# CPU_Module.net
KiCad netlist of a schematic drawn in Altium Designer
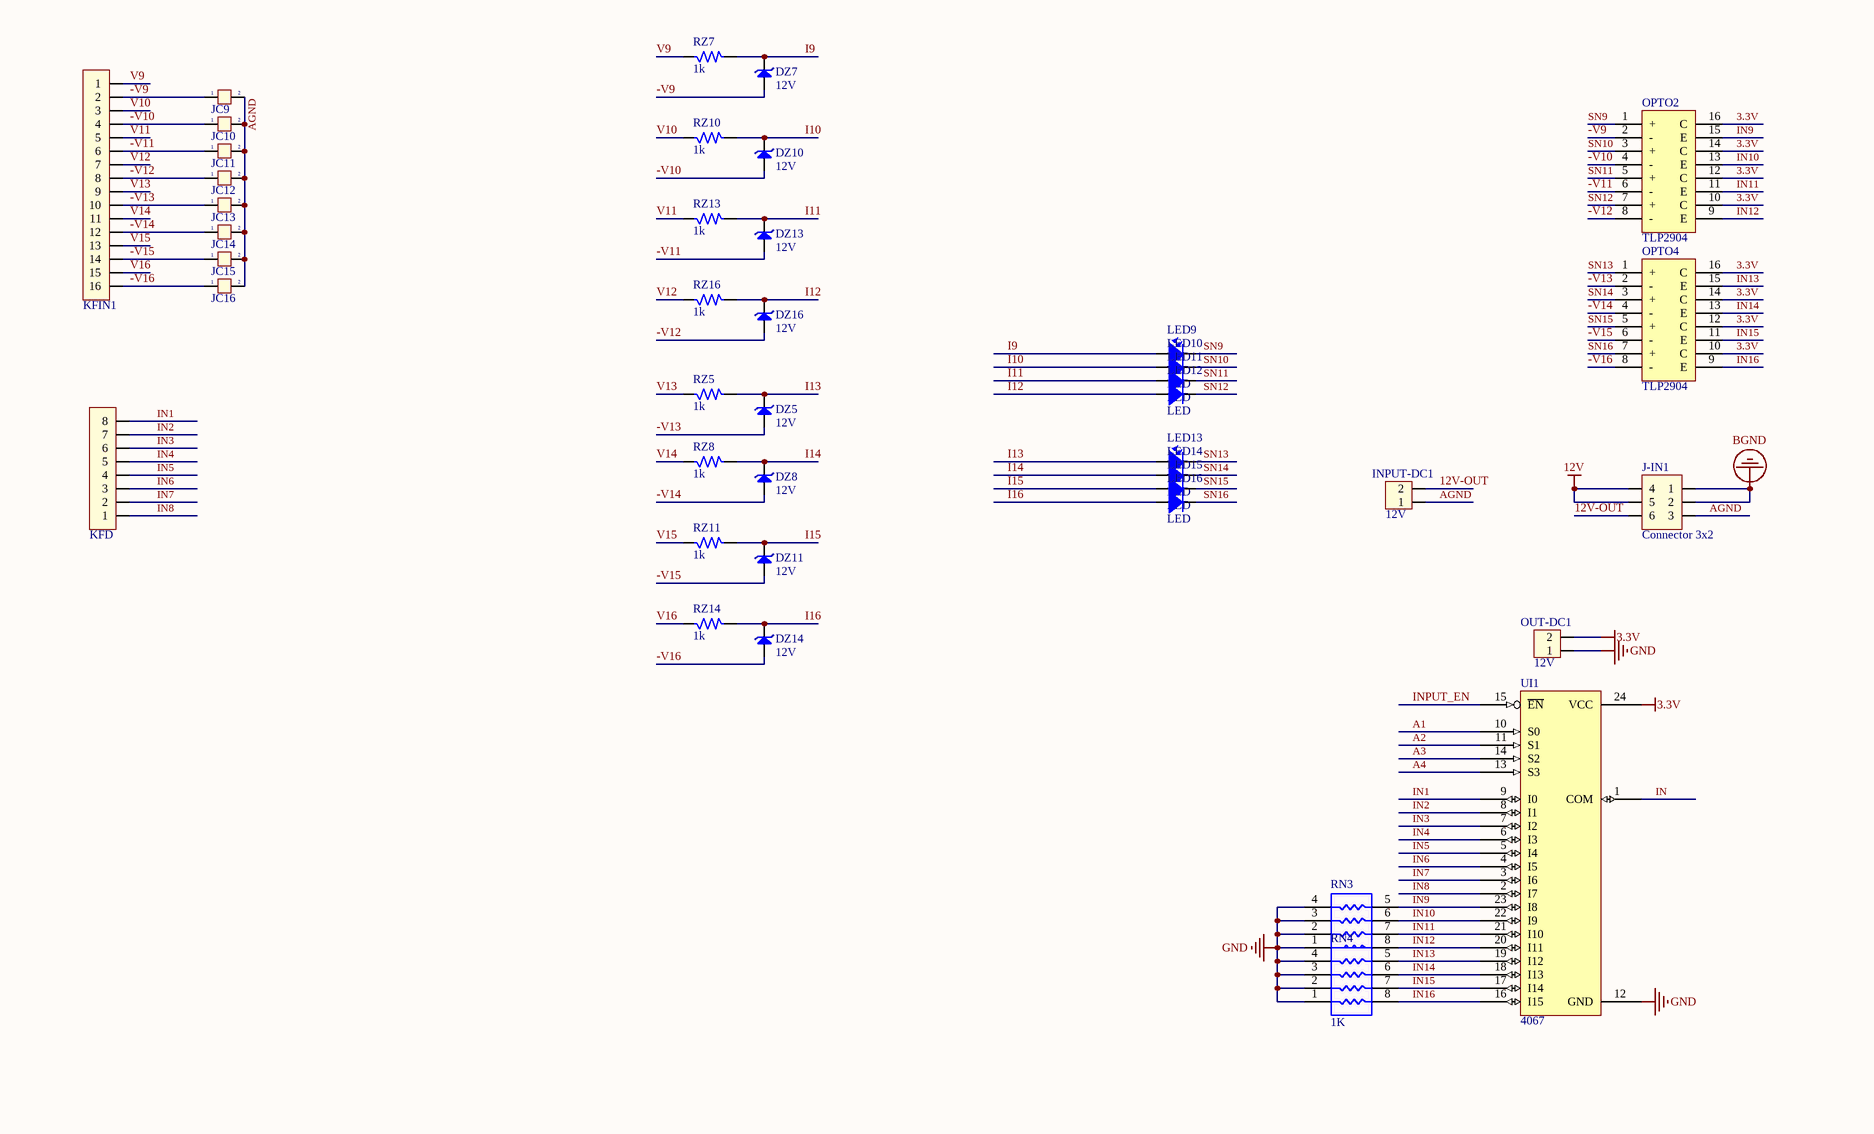
[diagram p0: CPU Module.SchDoc, top]
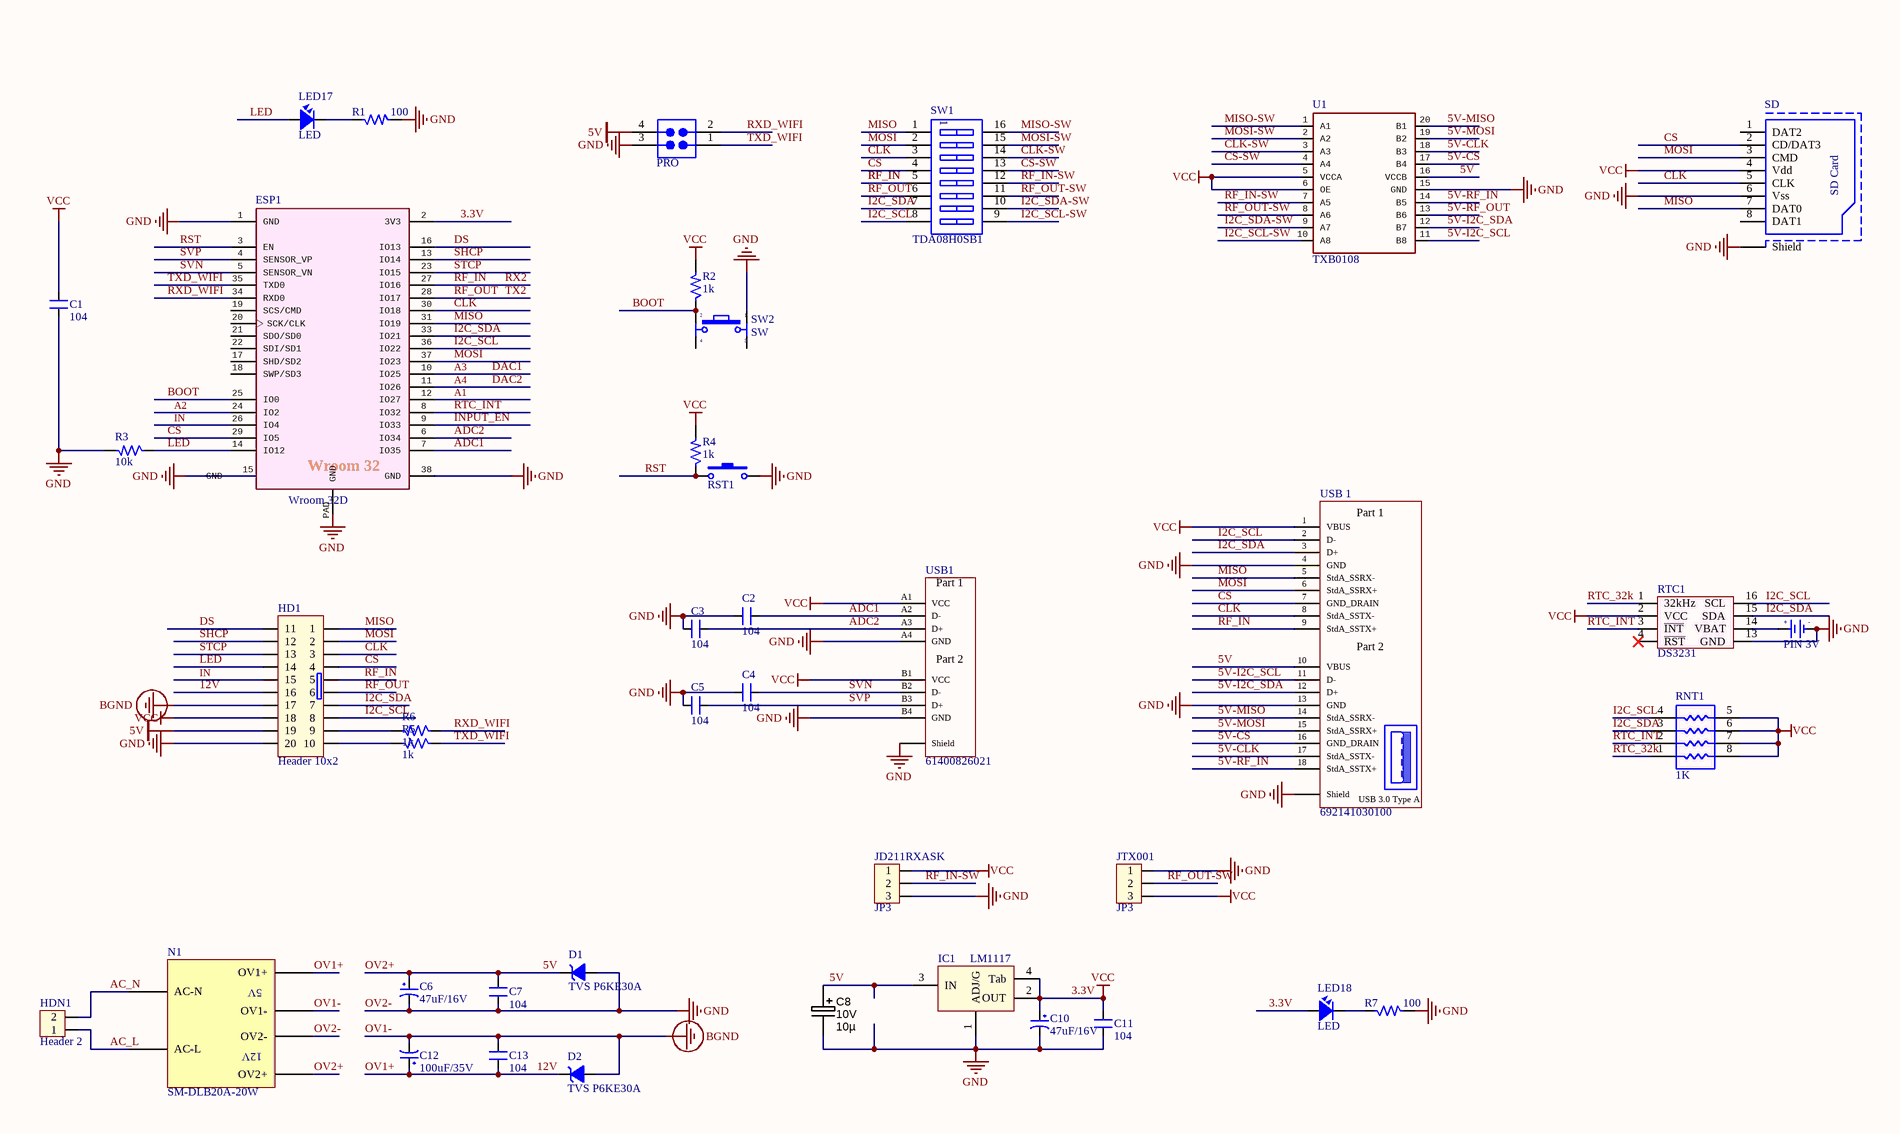
[diagram p1: CPU Module.SchDoc, bottom]

(export (version "E")
  (design (tool "Eeschema 10.0.6"))
  (components
    (comp (ref "BT1")
      (value "PIN 3V")
      (footprint "PIN CR1220-SMD")
      (description "Lithium Battery Holder for CR2032 3V Cell")
      (libsource (lib "Library") (part "PIN 3V"))
    )
    (comp (ref "C1")
      (value "104")
      (footprint "SM-0805")
      (description "Cap SMD")
      (libsource (lib "syhaunguyen") (part "CM"))
    )
    (comp (ref "C2")
      (value "104")
      (footprint "SM-0805")
      (description "Cap SMD")
      (libsource (lib "syhaunguyen") (part "CM"))
    )
    (comp (ref "C3")
      (value "104")
      (footprint "SM-0805")
      (description "Cap SMD")
      (libsource (lib "syhaunguyen") (part "CM"))
    )
    (comp (ref "C4")
      (value "104")
      (footprint "SM-0805")
      (description "Cap SMD")
      (libsource (lib "syhaunguyen") (part "CM"))
    )
    (comp (ref "C5")
      (value "104")
      (footprint "SM-0805")
      (description "Cap SMD")
      (libsource (lib "syhaunguyen") (part "CM"))
    )
    (comp (ref "C6")
      (value "47uF/16V")
      (footprint "WCAP-AS5H_6.3x5.5")
      (description "Cap 100uF/35V - 470uF/16V")
      (libsource (lib "syhaunguyen") (part "CP3"))
    )
    (comp (ref "C7")
      (value "104")
      (footprint "SM-0805")
      (description "Cap SMD")
      (libsource (lib "syhaunguyen") (part "CM"))
    )
    (comp (ref "C8")
      (value "10µ")
      (footprint "CAPMP3216X180N")
      (description "Capacitor SMD Tantalum 10uF 20% 10V 0805")
      (fields (field (name "TOLERANCE") "±20%") (field (name "RATINGS") "10V"))
      (libsource (lib "PBL - Capacitors") (part "CAPT_10u_0805_10V"))
    )
    (comp (ref "C10")
      (value "47uF/16V")
      (footprint "WCAP-AS5H_6.3x5.5")
      (description "Cap 100uF/35V - 470uF/16V")
      (libsource (lib "") (part "CP3_1"))
    )
    (comp (ref "C11")
      (value "104")
      (footprint "SM-0805")
      (description "Cap SMD")
      (libsource (lib "syhaunguyen") (part "CM"))
    )
    (comp (ref "C12")
      (value "100uF/35V")
      (footprint "WCAP-AS5H_8x10.5")
      (description "Cap 100uF/35V - 470uF/16V")
      (libsource (lib "syhaunguyen") (part "CP3"))
    )
    (comp (ref "C13")
      (value "104")
      (footprint "SM-0805")
      (description "Cap SMD")
      (libsource (lib "syhaunguyen") (part "CM"))
    )
    (comp (ref "D1")
      (value "TVS P6KE30A")
      (footprint "DO-214AA_Unidirectional")
      (description "Diode Zenner")
      (libsource (lib "syhaunguyen") (part "DZ"))
    )
    (comp (ref "D2")
      (value "TVS P6KE30A")
      (footprint "DO-214AA_Unidirectional")
      (description "Diode Zenner")
      (libsource (lib "syhaunguyen") (part "DZ"))
    )
    (comp (ref "DZ5")
      (value "12V")
      (footprint "DIOS 1S2P1406H")
      (description "DIODE GEN PURP 75V 200MA LLDS")
      (libsource (lib "Diode") (part "DIODE Zener"))
    )
    (comp (ref "DZ7")
      (value "12V")
      (footprint "DIOS 1S2P1406H")
      (description "DIODE GEN PURP 75V 200MA LLDS")
      (libsource (lib "Diode") (part "DIODE Zener"))
    )
    (comp (ref "DZ8")
      (value "12V")
      (footprint "DIOS 1S2P1406H")
      (description "DIODE GEN PURP 75V 200MA LLDS")
      (libsource (lib "Diode") (part "DIODE Zener"))
    )
    (comp (ref "DZ10")
      (value "12V")
      (footprint "DIOS 1S2P1406H")
      (description "DIODE GEN PURP 75V 200MA LLDS")
      (libsource (lib "Diode") (part "DIODE Zener"))
    )
    (comp (ref "DZ11")
      (value "12V")
      (footprint "DIOS 1S2P1406H")
      (description "DIODE GEN PURP 75V 200MA LLDS")
      (libsource (lib "Diode") (part "DIODE Zener"))
    )
    (comp (ref "DZ13")
      (value "12V")
      (footprint "DIOS 1S2P1406H")
      (description "DIODE GEN PURP 75V 200MA LLDS")
      (libsource (lib "Diode") (part "DIODE Zener"))
    )
    (comp (ref "DZ14")
      (value "12V")
      (footprint "DIOS 1S2P1406H")
      (description "DIODE GEN PURP 75V 200MA LLDS")
      (libsource (lib "Diode") (part "DIODE Zener"))
    )
    (comp (ref "DZ16")
      (value "12V")
      (footprint "DIOS 1S2P1406H")
      (description "DIODE GEN PURP 75V 200MA LLDS")
      (libsource (lib "Diode") (part "DIODE Zener"))
    )
    (comp (ref "ESP1")
      (value "Wroom 32D")
      (footprint "MODULE_ESP-WROOM-32")
      (fields (field (name "MF") "Olimex LTD") (field (name "MP") "ESP-WROOM-32"))
      (libsource (lib "ESP-WROOM-32") (part "ESP-WROOM-32"))
    )
    (comp (ref "HD1")
      (value "Header 10x2")
      (footprint "Hed2X10S")
      (libsource (lib "syhaunguyen") (part "HED10X2"))
    )
    (comp (ref "HDN1")
      (value "Header 2")
      (footprint "KF211V- 2")
      (description "Header 2 (Green)")
      (libsource (lib "syhaunguyen") (part "Hed2"))
    )
    (comp (ref "IC1")
      (value "LM1117")
      (footprint "SOT223-4N")
      (description "3v3")
      (libsource (lib "syhaunguyen") (part "LM1117"))
    )
    (comp (ref "INPUT-DC1")
      (value "12V")
      (footprint "KF211V- 2")
      (description "Header 2 (Green)")
      (libsource (lib "syhaunguyen") (part "Hed2"))
    )
    (comp (ref "J-IN1")
      (value "Connector 3x2")
      (footprint "JP3x2")
      (libsource (lib "syhaunguyen") (part "JP3x2"))
    )
    (comp (ref "JC9") (value "Jumper 2") (footprint "JP2") (libsource (lib "syhaunguyen") (part "JP 2")))
    (comp (ref "JC10") (value "Jumper 2") (footprint "JP2") (libsource (lib "syhaunguyen") (part "JP 2")))
    (comp (ref "JC11") (value "Jumper 2") (footprint "JP2") (libsource (lib "syhaunguyen") (part "JP 2")))
    (comp (ref "JC12") (value "Jumper 2") (footprint "JP2") (libsource (lib "syhaunguyen") (part "JP 2")))
    (comp (ref "JC13") (value "Jumper 2") (footprint "JP2") (libsource (lib "syhaunguyen") (part "JP 2")))
    (comp (ref "JC14") (value "Jumper 2") (footprint "JP2") (libsource (lib "syhaunguyen") (part "JP 2")))
    (comp (ref "JC15") (value "Jumper 2") (footprint "JP2") (libsource (lib "syhaunguyen") (part "JP 2")))
    (comp (ref "JC16") (value "Jumper 2") (footprint "JP2") (libsource (lib "syhaunguyen") (part "JP 2")))
    (comp (ref "JD211RXASK")
      (value "JP3")
      (footprint "JP3")
      (description "Connector 3")
      (libsource (lib "syhaunguyen") (part "Con3"))
    )
    (comp (ref "JTX001")
      (value "JP3")
      (footprint "JP3")
      (description "Connector 3")
      (libsource (lib "syhaunguyen") (part "Con3"))
    )
    (comp (ref "KFD")
      (value "Header 8")
      (footprint "KF211V- 8")
      (description "KF211R-5.0")
      (libsource (lib "Sonbui") (part "KF 8"))
    )
    (comp (ref "KFIN1")
      (value "Header 16")
      (footprint "KF211V- 16")
      (description "KF211R-5.0")
      (libsource (lib "Sonbui") (part "KF 16"))
    )
    (comp (ref "LED9")
      (value "LED")
      (footprint "LED0805")
      (description "LED Single colour Green and Red")
      (libsource (lib "syhaunguyen") (part "LED"))
    )
    (comp (ref "LED10")
      (value "LED")
      (footprint "LED0805")
      (description "LED Single colour Green and Red")
      (libsource (lib "syhaunguyen") (part "LED"))
    )
    (comp (ref "LED11")
      (value "LED")
      (footprint "LED0805")
      (description "LED Single colour Green and Red")
      (libsource (lib "syhaunguyen") (part "LED"))
    )
    (comp (ref "LED12")
      (value "LED")
      (footprint "LED0805")
      (description "LED Single colour Green and Red")
      (libsource (lib "syhaunguyen") (part "LED"))
    )
    (comp (ref "LED13")
      (value "LED")
      (footprint "LED0805")
      (description "LED Single colour Green and Red")
      (libsource (lib "syhaunguyen") (part "LED"))
    )
    (comp (ref "LED14")
      (value "LED")
      (footprint "LED0805")
      (description "LED Single colour Green and Red")
      (libsource (lib "syhaunguyen") (part "LED"))
    )
    (comp (ref "LED15")
      (value "LED")
      (footprint "LED0805")
      (description "LED Single colour Green and Red")
      (libsource (lib "syhaunguyen") (part "LED"))
    )
    (comp (ref "LED16")
      (value "LED")
      (footprint "LED0805")
      (description "LED Single colour Green and Red")
      (libsource (lib "syhaunguyen") (part "LED"))
    )
    (comp (ref "LED17")
      (value "LED")
      (footprint "LED0805")
      (description "LED Single colour Green and Red")
      (libsource (lib "syhaunguyen") (part "LED"))
    )
    (comp (ref "LED18")
      (value "LED")
      (footprint "LED0805")
      (description "LED Single colour Green and Red")
      (libsource (lib "syhaunguyen") (part "LED"))
    )
    (comp (ref "N1")
      (value "SM-DLB20A-20W")
      (footprint "SM-DLB20A")
      (libsource (lib "AC-DC Module") (part "SM-DLB20A-20W"))
    )
    (comp (ref "OPTO2")
      (value "TLP2904")
      (footprint "SO-16")
      (description "PC817 OPTO")
      (libsource (lib "Cty1") (part "PC817 x 4"))
    )
    (comp (ref "OPTO4")
      (value "TLP2904")
      (footprint "SO-16")
      (description "PC817 OPTO")
      (libsource (lib "Cty1") (part "PC817 x 4"))
    )
    (comp (ref "OUT-DC1")
      (value "12V")
      (footprint "KF211V- 2")
      (description "Header 2 (Green)")
      (libsource (lib "syhaunguyen") (part "Hed2"))
    )
    (comp (ref "PRO")
      (value "61300421821")
      (footprint "61300421121")
      (description "2.54 mm Dual Socket Header, 04p")
      (fields (field (name "PUBLISHER") "Wurth Elektronik"))
      (libsource (lib "JUMPER") (part "JP2x2 2.54MM"))
    )
    (comp (ref "R1")
      (value "100")
      (footprint "R-0805")
      (description "Resistor 1/4W")
      (libsource (lib "heromap") (part "R"))
    )
    (comp (ref "R2")
      (value "1k")
      (footprint "R-0805")
      (description "Resistor 1/4W")
      (libsource (lib "heromap") (part "R"))
    )
    (comp (ref "R3")
      (value "10k")
      (footprint "R-0805")
      (description "Resistor 1/4W")
      (libsource (lib "heromap") (part "R"))
    )
    (comp (ref "R4")
      (value "1k")
      (footprint "R-0805")
      (description "Resistor 1/4W")
      (libsource (lib "heromap") (part "R"))
    )
    (comp (ref "R5")
      (value "1k")
      (footprint "R-0805")
      (description "Resistor 1/4W")
      (libsource (lib "heromap") (part "R"))
    )
    (comp (ref "R6")
      (value "1k")
      (footprint "R-0805")
      (description "Resistor 1/4W")
      (libsource (lib "heromap") (part "R"))
    )
    (comp (ref "R7")
      (value "100")
      (footprint "R-0805")
      (description "Resistor 1/4W")
      (libsource (lib "heromap") (part "R"))
    )
    (comp (ref "RN3")
      (value "1K")
      (footprint "RES P4 Dual 0805/2012")
      (libsource (lib "Resistor") (part "Respack 4 Dual"))
    )
    (comp (ref "RN4")
      (value "1K")
      (footprint "RES P4 Dual 0805/2012")
      (libsource (lib "Resistor") (part "Respack 4 Dual"))
    )
    (comp (ref "RNT1")
      (value "1K")
      (footprint "RES P4 Dual 0805/2012")
      (libsource (lib "Resistor") (part "Respack 4 Dual"))
    )
    (comp (ref "RST1")
      (value "SW-SMD")
      (footprint "SW-SMD")
      (description "Switch")
      (fields (field (name "PUBLISHER") "Altium Limited"))
      (libsource (lib "Schematic") (part "SW-SMD"))
    )
    (comp (ref "RTC1")
      (value "DS3231")
      (footprint "SOIC127P750X1030-16N")
      (description "I2C RTC/TCXO/Crystal")
      (libsource (lib "Ics") (part "DS3231"))
    )
    (comp (ref "RZ5")
      (value "1k")
      (footprint "SM-1206")
      (description "Resistor 1/4W")
      (libsource (lib "syhaunguyen") (part "R"))
    )
    (comp (ref "RZ7")
      (value "1k")
      (footprint "SM-1206")
      (description "Resistor 1/4W")
      (libsource (lib "syhaunguyen") (part "R"))
    )
    (comp (ref "RZ8")
      (value "1k")
      (footprint "SM-1206")
      (description "Resistor 1/4W")
      (libsource (lib "syhaunguyen") (part "R"))
    )
    (comp (ref "RZ10")
      (value "1k")
      (footprint "SM-1206")
      (description "Resistor 1/4W")
      (libsource (lib "syhaunguyen") (part "R"))
    )
    (comp (ref "RZ11")
      (value "1k")
      (footprint "SM-1206")
      (description "Resistor 1/4W")
      (libsource (lib "syhaunguyen") (part "R"))
    )
    (comp (ref "RZ13")
      (value "1k")
      (footprint "SM-1206")
      (description "Resistor 1/4W")
      (libsource (lib "syhaunguyen") (part "R"))
    )
    (comp (ref "RZ14")
      (value "1k")
      (footprint "SM-1206")
      (description "Resistor 1/4W")
      (libsource (lib "syhaunguyen") (part "R"))
    )
    (comp (ref "RZ16")
      (value "1k")
      (footprint "SM-1206")
      (description "Resistor 1/4W")
      (libsource (lib "syhaunguyen") (part "R"))
    )
    (comp (ref "SD")
      (value "693072010801")
      (footprint "693072010801")
      (description "Micro SD Card Connector - Hinge - 8 pins")
      (fields (field (name "PUBLISHER") "Wurth Elektronik"))
      (libsource (lib "Card") (part "SD-693072010801"))
    )
    (comp (ref "SW1")
      (value "TDA08H0SB1")
      (footprint "SW8-416131160808")
      (description "WS-DITV 2.54 mm small compact THT with raised actuator, 8p")
      (fields (field (name "PART NUMBER") "418127270908") (field (name "PUBLISHER") "Wurth Elektronik"))
      (libsource (lib "Switch") (part "SW 8P"))
    )
    (comp (ref "SW2")
      (value "SW")
      (footprint "SW2-D2")
      (description "Switch button 4 pin")
      (libsource (lib "ESP8266_CD4051") (part "SW4"))
    )
    (comp (ref "U1")
      (value "TXB0108")
      (footprint "TSSOP65P440X650-20N")
      (fields (field (name "MF") "Texas Instruments"))
      (libsource (lib "TXB0108") (part "TXB0108"))
    )
    (comp (ref "UI1")
      (value "4067")
      (footprint "SSOP65P530X850-24N")
      (description "MUX-74HC4067")
      (libsource (lib "CustomLibrary") (part "MUX-74HC4067"))
    )
    (comp (ref "USB 1")
      (value "692141030100")
      (footprint "692141030100")
      (description "USB 3.0 Type A")
      (fields (field (name "PUBLISHER") "Wurth Elektronik"))
      (libsource (lib "Usb") (part "USB 3.0 Type A Female THR Stacked"))
    )
    (comp (ref "USB1")
      (value "61400826021")
      (footprint "61400826021")
      (description "USB 2.0 Type A Female THR Stacked")
      (fields (field (name "PUBLISHER") "Wurth Elektronik"))
      (libsource (lib "Usb") (part "USB 2.0 Type A Female THR Stacked"))
    )
  )
  (nets
    (net (code "1") (name "/-V9") (class "Default")
      (node (ref "DZ7") (pin "1") (pinfunction "A_1") (pintype "passive"))
      (node (ref "JC9") (pin "1") (pinfunction "1_1") (pintype "passive"))
      (node (ref "KFIN1") (pin "2") (pinfunction "2_2") (pintype "passive"))
      (node (ref "OPTO2") (pin "2") (pinfunction "-_2") (pintype "passive"))
    )
    (net (code "2") (name "/-V10") (class "Default")
      (node (ref "DZ10") (pin "1") (pinfunction "A_1") (pintype "passive"))
      (node (ref "JC10") (pin "1") (pinfunction "1_1") (pintype "passive"))
      (node (ref "KFIN1") (pin "4") (pinfunction "4_4") (pintype "passive"))
      (node (ref "OPTO2") (pin "4") (pinfunction "-_4") (pintype "passive"))
    )
    (net (code "3") (name "/-V11") (class "Default")
      (node (ref "DZ13") (pin "1") (pinfunction "A_1") (pintype "passive"))
      (node (ref "JC11") (pin "1") (pinfunction "1_1") (pintype "passive"))
      (node (ref "KFIN1") (pin "6") (pinfunction "6_6") (pintype "passive"))
      (node (ref "OPTO2") (pin "6") (pinfunction "-_6") (pintype "passive"))
    )
    (net (code "4") (name "/-V12") (class "Default")
      (node (ref "DZ16") (pin "1") (pinfunction "A_1") (pintype "passive"))
      (node (ref "JC12") (pin "1") (pinfunction "1_1") (pintype "passive"))
      (node (ref "KFIN1") (pin "8") (pinfunction "8_8") (pintype "passive"))
      (node (ref "OPTO2") (pin "8") (pinfunction "-_8") (pintype "passive"))
    )
    (net (code "5") (name "/-V13") (class "Default")
      (node (ref "DZ5") (pin "1") (pinfunction "A_1") (pintype "passive"))
      (node (ref "JC13") (pin "1") (pinfunction "1_1") (pintype "passive"))
      (node (ref "KFIN1") (pin "10") (pinfunction "10_10") (pintype "passive"))
      (node (ref "OPTO4") (pin "2") (pinfunction "-_2") (pintype "passive"))
    )
    (net (code "6") (name "/-V14") (class "Default")
      (node (ref "DZ8") (pin "1") (pinfunction "A_1") (pintype "passive"))
      (node (ref "JC14") (pin "1") (pinfunction "1_1") (pintype "passive"))
      (node (ref "KFIN1") (pin "12") (pinfunction "12_12") (pintype "passive"))
      (node (ref "OPTO4") (pin "4") (pinfunction "-_4") (pintype "passive"))
    )
    (net (code "7") (name "/-V15") (class "Default")
      (node (ref "DZ11") (pin "1") (pinfunction "A_1") (pintype "passive"))
      (node (ref "JC15") (pin "1") (pinfunction "1_1") (pintype "passive"))
      (node (ref "KFIN1") (pin "14") (pinfunction "14_14") (pintype "passive"))
      (node (ref "OPTO4") (pin "6") (pinfunction "-_6") (pintype "passive"))
    )
    (net (code "8") (name "/-V16") (class "Default")
      (node (ref "DZ14") (pin "1") (pinfunction "A_1") (pintype "passive"))
      (node (ref "JC16") (pin "1") (pinfunction "1_1") (pintype "passive"))
      (node (ref "KFIN1") (pin "16") (pinfunction "16_16") (pintype "passive"))
      (node (ref "OPTO4") (pin "8") (pinfunction "-_8") (pintype "passive"))
    )
    (net (code "9") (name "/5V-CLK") (class "Default")
      (node (ref "U1") (pin "18") (pinfunction "B3_18") (pintype "passive"))
      (node (ref "USB 1") (pin "17") (pinfunction "StdA_SSTX-_17") (pintype "passive"))
    )
    (net (code "10") (name "/5V-CS") (class "Default")
      (node (ref "U1") (pin "17") (pinfunction "B4_17") (pintype "passive"))
      (node (ref "USB 1") (pin "16") (pinfunction "GND_DRAIN_16") (pintype "passive"))
    )
    (net (code "11") (name "/5V-I2C_SCL") (class "Default")
      (node (ref "U1") (pin "11") (pinfunction "B8_11") (pintype "passive"))
      (node (ref "USB 1") (pin "11") (pinfunction "D-_11") (pintype "passive"))
    )
    (net (code "12") (name "/5V-I2C_SDA") (class "Default")
      (node (ref "U1") (pin "12") (pinfunction "B7_12") (pintype "passive"))
      (node (ref "USB 1") (pin "12") (pinfunction "D+_12") (pintype "passive"))
    )
    (net (code "13") (name "/5V-MISO") (class "Default")
      (node (ref "U1") (pin "20") (pinfunction "B1_20") (pintype "passive"))
      (node (ref "USB 1") (pin "14") (pinfunction "StdA_SSRX-_14") (pintype "passive"))
    )
    (net (code "14") (name "/5V-MOSI") (class "Default")
      (node (ref "U1") (pin "19") (pinfunction "B2_19") (pintype "passive"))
      (node (ref "USB 1") (pin "15") (pinfunction "StdA_SSRX+_15") (pintype "passive"))
    )
    (net (code "15") (name "/5V-RF_IN") (class "Default")
      (node (ref "U1") (pin "14") (pinfunction "B5_14") (pintype "passive"))
      (node (ref "USB 1") (pin "18") (pinfunction "StdA_SSTX+_18") (pintype "passive"))
    )
    (net (code "16") (name "/5V-RF_OUT") (class "Default")
      (node (ref "U1") (pin "13") (pinfunction "B6_13") (pintype "passive"))
    )
    (net (code "17") (name "/12V-OUT") (class "Default")
      (node (ref "INPUT-DC1") (pin "2") (pinfunction "2_2") (pintype "passive"))
      (node (ref "J-IN1") (pin "6") (pinfunction "6_6") (pintype "passive"))
    )
    (net (code "18") (name "/A1") (class "Default")
      (node (ref "ESP1") (pin "12") (pinfunction "IO27_12") (pintype "passive"))
      (node (ref "UI1") (pin "10") (pinfunction "S0_10") (pintype "input"))
    )
    (net (code "19") (name "/A2") (class "Default")
      (node (ref "ESP1") (pin "24") (pinfunction "IO2_24") (pintype "passive"))
      (node (ref "UI1") (pin "11") (pinfunction "S1_11") (pintype "input"))
    )
    (net (code "20") (name "/A3") (class "Default")
      (node (ref "ESP1") (pin "10") (pinfunction "IO25_10") (pintype "passive"))
      (node (ref "UI1") (pin "14") (pinfunction "S2_14") (pintype "input"))
    )
    (net (code "21") (name "/A4") (class "Default")
      (node (ref "ESP1") (pin "11") (pinfunction "IO26_11") (pintype "passive"))
      (node (ref "UI1") (pin "13") (pinfunction "S3_13") (pintype "input"))
    )
    (net (code "22") (name "/AC_L") (class "Default")
      (node (ref "HDN1") (pin "1") (pinfunction "1_1") (pintype "passive"))
      (node (ref "N1") (pin "AC-L") (pinfunction "AC-L_AC-L") (pintype "passive"))
    )
    (net (code "23") (name "/AC_N") (class "Default")
      (node (ref "HDN1") (pin "2") (pinfunction "2_2") (pintype "passive"))
      (node (ref "N1") (pin "AC-N") (pinfunction "AC-N_AC-N") (pintype "passive"))
    )
    (net (code "24") (name "/ADC1") (class "Default")
      (node (ref "C2") (pin "1") (pinfunction "1_1") (pintype "passive"))
      (node (ref "ESP1") (pin "7") (pinfunction "IO35_7") (pintype "passive"))
      (node (ref "USB1") (pin "A2") (pinfunction "D-_A2") (pintype "passive"))
    )
    (net (code "25") (name "/ADC2") (class "Default")
      (node (ref "C3") (pin "2") (pinfunction "2_2") (pintype "passive"))
      (node (ref "ESP1") (pin "6") (pinfunction "IO34_6") (pintype "passive"))
      (node (ref "USB1") (pin "A3") (pinfunction "D+_A3") (pintype "passive"))
    )
    (net (code "26") (name "/AGND") (class "Default")
      (node (ref "INPUT-DC1") (pin "1") (pinfunction "1_1") (pintype "passive"))
      (node (ref "J-IN1") (pin "3") (pinfunction "3_3") (pintype "passive"))
      (node (ref "JC10") (pin "2") (pinfunction "2_2") (pintype "passive"))
      (node (ref "JC11") (pin "2") (pinfunction "2_2") (pintype "passive"))
      (node (ref "JC12") (pin "2") (pinfunction "2_2") (pintype "passive"))
      (node (ref "JC13") (pin "2") (pinfunction "2_2") (pintype "passive"))
      (node (ref "JC14") (pin "2") (pinfunction "2_2") (pintype "passive"))
      (node (ref "JC15") (pin "2") (pinfunction "2_2") (pintype "passive"))
      (node (ref "JC16") (pin "2") (pinfunction "2_2") (pintype "passive"))
      (node (ref "JC9") (pin "2") (pinfunction "2_2") (pintype "passive"))
    )
    (net (code "27") (name "/BOOT") (class "Default")
      (node (ref "ESP1") (pin "25") (pinfunction "IO0_25") (pintype "passive"))
      (node (ref "R2") (pin "1") (pinfunction "1_1") (pintype "passive"))
      (node (ref "SW2") (pin "2") (pinfunction "2_2") (pintype "passive"))
    )
    (net (code "28") (name "/CLK") (class "Default")
      (node (ref "ESP1") (pin "30") (pinfunction "IO18_30") (pintype "passive"))
      (node (ref "HD1") (pin "3") (pinfunction "3_3") (pintype "passive"))
      (node (ref "SD") (pin "5") (pinfunction "CLK_5") (pintype "passive"))
      (node (ref "SW1") (pin "3") (pinfunction "3_3") (pintype "passive"))
      (node (ref "USB 1") (pin "8") (pinfunction "StdA_SSTX-_8") (pintype "passive"))
    )
    (net (code "29") (name "/CLK-SW") (class "Default")
      (node (ref "SW1") (pin "14") (pinfunction "14_14") (pintype "passive"))
      (node (ref "U1") (pin "3") (pinfunction "A3_3") (pintype "passive"))
    )
    (net (code "30") (name "/CS") (class "Default")
      (node (ref "ESP1") (pin "29") (pinfunction "IO5_29") (pintype "passive"))
      (node (ref "HD1") (pin "4") (pinfunction "4_4") (pintype "passive"))
      (node (ref "SD") (pin "2") (pinfunction "CD/DAT3_2") (pintype "passive"))
      (node (ref "SW1") (pin "4") (pinfunction "4_4") (pintype "passive"))
      (node (ref "USB 1") (pin "7") (pinfunction "GND_DRAIN_7") (pintype "passive"))
    )
    (net (code "31") (name "/CS-SW") (class "Default")
      (node (ref "SW1") (pin "13") (pinfunction "13_13") (pintype "passive"))
      (node (ref "U1") (pin "4") (pinfunction "A4_4") (pintype "passive"))
    )
    (net (code "32") (name "/DS") (class "Default")
      (node (ref "ESP1") (pin "16") (pinfunction "IO13_16") (pintype "passive"))
      (node (ref "HD1") (pin "11") (pinfunction "11_11") (pintype "passive"))
    )
    (net (code "33") (name "/I2C_SCL") (class "Default")
      (node (ref "ESP1") (pin "36") (pinfunction "IO22_36") (pintype "passive"))
      (node (ref "HD1") (pin "8") (pinfunction "8_8") (pintype "passive"))
      (node (ref "RNT1") (pin "4") (pinfunction "4_4") (pintype "passive"))
      (node (ref "RTC1") (pin "16") (pinfunction "SCL_16") (pintype "passive"))
      (node (ref "SW1") (pin "8") (pinfunction "8_8") (pintype "passive"))
      (node (ref "USB 1") (pin "2") (pinfunction "D-_2") (pintype "passive"))
    )
    (net (code "34") (name "/I2C_SCL-SW") (class "Default")
      (node (ref "SW1") (pin "9") (pinfunction "9_9") (pintype "passive"))
      (node (ref "U1") (pin "10") (pinfunction "A8_10") (pintype "passive"))
    )
    (net (code "35") (name "/I2C_SDA") (class "Default")
      (node (ref "ESP1") (pin "33") (pinfunction "IO21_33") (pintype "passive"))
      (node (ref "HD1") (pin "7") (pinfunction "7_7") (pintype "passive"))
      (node (ref "RNT1") (pin "3") (pinfunction "3_3") (pintype "passive"))
      (node (ref "RTC1") (pin "15") (pinfunction "SDA_15") (pintype "passive"))
      (node (ref "SW1") (pin "7") (pinfunction "7_7") (pintype "passive"))
      (node (ref "USB 1") (pin "3") (pinfunction "D+_3") (pintype "passive"))
    )
    (net (code "36") (name "/I2C_SDA-SW") (class "Default")
      (node (ref "SW1") (pin "10") (pinfunction "10_10") (pintype "passive"))
      (node (ref "U1") (pin "9") (pinfunction "A7_9") (pintype "passive"))
    )
    (net (code "37") (name "/I9") (class "Default")
      (node (ref "DZ7") (pin "2") (pinfunction "K_2") (pintype "passive"))
      (node (ref "LED9") (pin "1") (pinfunction "1_1") (pintype "passive"))
      (node (ref "RZ7") (pin "2") (pinfunction "2_2") (pintype "passive"))
    )
    (net (code "38") (name "/I10") (class "Default")
      (node (ref "DZ10") (pin "2") (pinfunction "K_2") (pintype "passive"))
      (node (ref "LED10") (pin "1") (pinfunction "1_1") (pintype "passive"))
      (node (ref "RZ10") (pin "2") (pinfunction "2_2") (pintype "passive"))
    )
    (net (code "39") (name "/I11") (class "Default")
      (node (ref "DZ13") (pin "2") (pinfunction "K_2") (pintype "passive"))
      (node (ref "LED11") (pin "1") (pinfunction "1_1") (pintype "passive"))
      (node (ref "RZ13") (pin "2") (pinfunction "2_2") (pintype "passive"))
    )
    (net (code "40") (name "/I12") (class "Default")
      (node (ref "DZ16") (pin "2") (pinfunction "K_2") (pintype "passive"))
      (node (ref "LED12") (pin "1") (pinfunction "1_1") (pintype "passive"))
      (node (ref "RZ16") (pin "2") (pinfunction "2_2") (pintype "passive"))
    )
    (net (code "41") (name "/I13") (class "Default")
      (node (ref "DZ5") (pin "2") (pinfunction "K_2") (pintype "passive"))
      (node (ref "LED13") (pin "1") (pinfunction "1_1") (pintype "passive"))
      (node (ref "RZ5") (pin "2") (pinfunction "2_2") (pintype "passive"))
    )
    (net (code "42") (name "/I14") (class "Default")
      (node (ref "DZ8") (pin "2") (pinfunction "K_2") (pintype "passive"))
      (node (ref "LED14") (pin "1") (pinfunction "1_1") (pintype "passive"))
      (node (ref "RZ8") (pin "2") (pinfunction "2_2") (pintype "passive"))
    )
    (net (code "43") (name "/I15") (class "Default")
      (node (ref "DZ11") (pin "2") (pinfunction "K_2") (pintype "passive"))
      (node (ref "LED15") (pin "1") (pinfunction "1_1") (pintype "passive"))
      (node (ref "RZ11") (pin "2") (pinfunction "2_2") (pintype "passive"))
    )
    (net (code "44") (name "/I16") (class "Default")
      (node (ref "DZ14") (pin "2") (pinfunction "K_2") (pintype "passive"))
      (node (ref "LED16") (pin "1") (pinfunction "1_1") (pintype "passive"))
      (node (ref "RZ14") (pin "2") (pinfunction "2_2") (pintype "passive"))
    )
    (net (code "45") (name "/IN") (class "Default")
      (node (ref "ESP1") (pin "26") (pinfunction "IO4_26") (pintype "passive"))
      (node (ref "HD1") (pin "15") (pinfunction "15_15") (pintype "passive"))
      (node (ref "UI1") (pin "1") (pinfunction "COM_1") (pintype "bidirectional"))
    )
    (net (code "46") (name "/IN1") (class "Default")
      (node (ref "KFD") (pin "8") (pinfunction "8_8") (pintype "passive"))
      (node (ref "UI1") (pin "9") (pinfunction "I0_9") (pintype "bidirectional"))
    )
    (net (code "47") (name "/IN2") (class "Default")
      (node (ref "KFD") (pin "7") (pinfunction "7_7") (pintype "passive"))
      (node (ref "UI1") (pin "8") (pinfunction "I1_8") (pintype "bidirectional"))
    )
    (net (code "48") (name "/IN3") (class "Default")
      (node (ref "KFD") (pin "6") (pinfunction "6_6") (pintype "passive"))
      (node (ref "UI1") (pin "7") (pinfunction "I2_7") (pintype "bidirectional"))
    )
    (net (code "49") (name "/IN4") (class "Default")
      (node (ref "KFD") (pin "5") (pinfunction "5_5") (pintype "passive"))
      (node (ref "UI1") (pin "6") (pinfunction "I3_6") (pintype "bidirectional"))
    )
    (net (code "50") (name "/IN5") (class "Default")
      (node (ref "KFD") (pin "4") (pinfunction "4_4") (pintype "passive"))
      (node (ref "UI1") (pin "5") (pinfunction "I4_5") (pintype "bidirectional"))
    )
    (net (code "51") (name "/IN6") (class "Default")
      (node (ref "KFD") (pin "3") (pinfunction "3_3") (pintype "passive"))
      (node (ref "UI1") (pin "4") (pinfunction "I5_4") (pintype "bidirectional"))
    )
    (net (code "52") (name "/IN7") (class "Default")
      (node (ref "KFD") (pin "2") (pinfunction "2_2") (pintype "passive"))
      (node (ref "UI1") (pin "3") (pinfunction "I6_3") (pintype "bidirectional"))
    )
    (net (code "53") (name "/IN8") (class "Default")
      (node (ref "KFD") (pin "1") (pinfunction "1_1") (pintype "passive"))
      (node (ref "UI1") (pin "2") (pinfunction "I7_2") (pintype "bidirectional"))
    )
    (net (code "54") (name "/IN9") (class "Default")
      (node (ref "OPTO2") (pin "15") (pinfunction "E_15") (pintype "passive"))
      (node (ref "RN3") (pin "5") (pinfunction "5_5") (pintype "passive"))
      (node (ref "UI1") (pin "23") (pinfunction "I8_23") (pintype "bidirectional"))
    )
    (net (code "55") (name "/IN10") (class "Default")
      (node (ref "OPTO2") (pin "13") (pinfunction "E_13") (pintype "passive"))
      (node (ref "RN3") (pin "6") (pinfunction "6_6") (pintype "passive"))
      (node (ref "UI1") (pin "22") (pinfunction "I9_22") (pintype "bidirectional"))
    )
    (net (code "56") (name "/IN11") (class "Default")
      (node (ref "OPTO2") (pin "11") (pinfunction "E_11") (pintype "passive"))
      (node (ref "RN3") (pin "7") (pinfunction "7_7") (pintype "passive"))
      (node (ref "UI1") (pin "21") (pinfunction "I10_21") (pintype "bidirectional"))
    )
    (net (code "57") (name "/IN12") (class "Default")
      (node (ref "OPTO2") (pin "9") (pinfunction "E_9") (pintype "passive"))
      (node (ref "RN3") (pin "8") (pinfunction "8_8") (pintype "passive"))
      (node (ref "UI1") (pin "20") (pinfunction "I11_20") (pintype "bidirectional"))
    )
    (net (code "58") (name "/IN13") (class "Default")
      (node (ref "OPTO4") (pin "15") (pinfunction "E_15") (pintype "passive"))
      (node (ref "RN4") (pin "5") (pinfunction "5_5") (pintype "passive"))
      (node (ref "UI1") (pin "19") (pinfunction "I12_19") (pintype "bidirectional"))
    )
    (net (code "59") (name "/IN14") (class "Default")
      (node (ref "OPTO4") (pin "13") (pinfunction "E_13") (pintype "passive"))
      (node (ref "RN4") (pin "6") (pinfunction "6_6") (pintype "passive"))
      (node (ref "UI1") (pin "18") (pinfunction "I13_18") (pintype "bidirectional"))
    )
    (net (code "60") (name "/IN15") (class "Default")
      (node (ref "OPTO4") (pin "11") (pinfunction "E_11") (pintype "passive"))
      (node (ref "RN4") (pin "7") (pinfunction "7_7") (pintype "passive"))
      (node (ref "UI1") (pin "17") (pinfunction "I14_17") (pintype "bidirectional"))
    )
    (net (code "61") (name "/IN16") (class "Default")
      (node (ref "OPTO4") (pin "9") (pinfunction "E_9") (pintype "passive"))
      (node (ref "RN4") (pin "8") (pinfunction "8_8") (pintype "passive"))
      (node (ref "UI1") (pin "16") (pinfunction "I15_16") (pintype "bidirectional"))
    )
    (net (code "62") (name "/INPUT_EN") (class "Default")
      (node (ref "ESP1") (pin "9") (pinfunction "IO33_9") (pintype "passive"))
      (node (ref "UI1") (pin "15") (pinfunction "~{EN}_15") (pintype "input"))
    )
    (net (code "63") (name "/LED") (class "Default")
      (node (ref "ESP1") (pin "14") (pinfunction "IO12_14") (pintype "passive"))
      (node (ref "HD1") (pin "14") (pinfunction "14_14") (pintype "passive"))
      (node (ref "LED17") (pin "1") (pinfunction "1_1") (pintype "passive"))
      (node (ref "R3") (pin "1") (pinfunction "1_1") (pintype "passive"))
    )
    (net (code "64") (name "/MISO") (class "Default")
      (node (ref "ESP1") (pin "31") (pinfunction "IO19_31") (pintype "passive"))
      (node (ref "HD1") (pin "1") (pinfunction "1_1") (pintype "passive"))
      (node (ref "SD") (pin "7") (pinfunction "DAT0_7") (pintype "passive"))
      (node (ref "SW1") (pin "1") (pinfunction "1_1") (pintype "passive"))
      (node (ref "USB 1") (pin "5") (pinfunction "StdA_SSRX-_5") (pintype "passive"))
    )
    (net (code "65") (name "/MISO-SW") (class "Default")
      (node (ref "SW1") (pin "16") (pinfunction "16_16") (pintype "passive"))
      (node (ref "U1") (pin "1") (pinfunction "A1_1") (pintype "passive"))
    )
    (net (code "66") (name "/MOSI") (class "Default")
      (node (ref "ESP1") (pin "37") (pinfunction "IO23_37") (pintype "passive"))
      (node (ref "HD1") (pin "2") (pinfunction "2_2") (pintype "passive"))
      (node (ref "SD") (pin "3") (pinfunction "CMD_3") (pintype "passive"))
      (node (ref "SW1") (pin "2") (pinfunction "2_2") (pintype "passive"))
      (node (ref "USB 1") (pin "6") (pinfunction "StdA_SSRX+_6") (pintype "passive"))
    )
    (net (code "67") (name "/MOSI-SW") (class "Default")
      (node (ref "SW1") (pin "15") (pinfunction "15_15") (pintype "passive"))
      (node (ref "U1") (pin "2") (pinfunction "A2_2") (pintype "passive"))
    )
    (net (code "68") (name "/RF_IN") (class "Default")
      (node (ref "ESP1") (pin "27") (pinfunction "IO16_27") (pintype "passive"))
      (node (ref "HD1") (pin "5") (pinfunction "5_5") (pintype "passive"))
      (node (ref "SW1") (pin "5") (pinfunction "5_5") (pintype "passive"))
      (node (ref "USB 1") (pin "9") (pinfunction "StdA_SSTX+_9") (pintype "passive"))
    )
    (net (code "69") (name "/RF_IN-SW") (class "Default")
      (node (ref "JD211RXASK") (pin "2") (pinfunction "2_2") (pintype "passive"))
      (node (ref "SW1") (pin "12") (pinfunction "12_12") (pintype "passive"))
      (node (ref "U1") (pin "7") (pinfunction "A5_7") (pintype "passive"))
    )
    (net (code "70") (name "/RF_OUT") (class "Default")
      (node (ref "ESP1") (pin "28") (pinfunction "IO17_28") (pintype "passive"))
      (node (ref "HD1") (pin "6") (pinfunction "6_6") (pintype "passive"))
      (node (ref "SW1") (pin "6") (pinfunction "6_6") (pintype "passive"))
    )
    (net (code "71") (name "/RF_OUT-SW") (class "Default")
      (node (ref "JTX001") (pin "2") (pinfunction "2_2") (pintype "passive"))
      (node (ref "SW1") (pin "11") (pinfunction "11_11") (pintype "passive"))
      (node (ref "U1") (pin "8") (pinfunction "A6_8") (pintype "passive"))
    )
    (net (code "72") (name "/RST") (class "Default")
      (node (ref "ESP1") (pin "3") (pinfunction "EN_3") (pintype "passive"))
      (node (ref "R4") (pin "1") (pinfunction "1_1") (pintype "passive"))
      (node (ref "RST1") (pin "1") (pinfunction "1_1") (pintype "passive"))
    )
    (net (code "73") (name "/RTC_32k") (class "Default")
      (node (ref "RNT1") (pin "1") (pinfunction "1_1") (pintype "passive"))
      (node (ref "RTC1") (pin "1") (pinfunction "32kHz_1") (pintype "passive"))
    )
    (net (code "74") (name "/RTC_INT") (class "Default")
      (node (ref "ESP1") (pin "8") (pinfunction "IO32_8") (pintype "passive"))
      (node (ref "RNT1") (pin "2") (pinfunction "2_2") (pintype "passive"))
      (node (ref "RTC1") (pin "3") (pinfunction "~{INT}_3") (pintype "passive"))
    )
    (net (code "75") (name "/RXD_WIFI") (class "Default")
      (node (ref "ESP1") (pin "34") (pinfunction "RXD0_34") (pintype "passive"))
      (node (ref "PRO") (pin "2") (pinfunction "2_2") (pintype "passive"))
      (node (ref "R6") (pin "1") (pinfunction "1_1") (pintype "passive"))
    )
    (net (code "76") (name "/SHCP") (class "Default")
      (node (ref "ESP1") (pin "13") (pinfunction "IO14_13") (pintype "passive"))
      (node (ref "HD1") (pin "12") (pinfunction "12_12") (pintype "passive"))
    )
    (net (code "77") (name "/SN9") (class "Default")
      (node (ref "LED9") (pin "2") (pinfunction "2_2") (pintype "passive"))
      (node (ref "OPTO2") (pin "1") (pinfunction "+_1") (pintype "passive"))
    )
    (net (code "78") (name "/SN10") (class "Default")
      (node (ref "LED10") (pin "2") (pinfunction "2_2") (pintype "passive"))
      (node (ref "OPTO2") (pin "3") (pinfunction "+_3") (pintype "passive"))
    )
    (net (code "79") (name "/SN11") (class "Default")
      (node (ref "LED11") (pin "2") (pinfunction "2_2") (pintype "passive"))
      (node (ref "OPTO2") (pin "5") (pinfunction "+_5") (pintype "passive"))
    )
    (net (code "80") (name "/SN12") (class "Default")
      (node (ref "LED12") (pin "2") (pinfunction "2_2") (pintype "passive"))
      (node (ref "OPTO2") (pin "7") (pinfunction "+_7") (pintype "passive"))
    )
    (net (code "81") (name "/SN13") (class "Default")
      (node (ref "LED13") (pin "2") (pinfunction "2_2") (pintype "passive"))
      (node (ref "OPTO4") (pin "1") (pinfunction "+_1") (pintype "passive"))
    )
    (net (code "82") (name "/SN14") (class "Default")
      (node (ref "LED14") (pin "2") (pinfunction "2_2") (pintype "passive"))
      (node (ref "OPTO4") (pin "3") (pinfunction "+_3") (pintype "passive"))
    )
    (net (code "83") (name "/SN15") (class "Default")
      (node (ref "LED15") (pin "2") (pinfunction "2_2") (pintype "passive"))
      (node (ref "OPTO4") (pin "5") (pinfunction "+_5") (pintype "passive"))
    )
    (net (code "84") (name "/SN16") (class "Default")
      (node (ref "LED16") (pin "2") (pinfunction "2_2") (pintype "passive"))
      (node (ref "OPTO4") (pin "7") (pinfunction "+_7") (pintype "passive"))
    )
    (net (code "85") (name "/STCP") (class "Default")
      (node (ref "ESP1") (pin "23") (pinfunction "IO15_23") (pintype "passive"))
      (node (ref "HD1") (pin "13") (pinfunction "13_13") (pintype "passive"))
    )
    (net (code "86") (name "/SVN") (class "Default")
      (node (ref "C4") (pin "1") (pinfunction "1_1") (pintype "passive"))
      (node (ref "ESP1") (pin "5") (pinfunction "SENSOR_VN_5") (pintype "passive"))
      (node (ref "USB1") (pin "B2") (pinfunction "D-_B2") (pintype "passive"))
    )
    (net (code "87") (name "/SVP") (class "Default")
      (node (ref "C5") (pin "2") (pinfunction "2_2") (pintype "passive"))
      (node (ref "ESP1") (pin "4") (pinfunction "SENSOR_VP_4") (pintype "passive"))
      (node (ref "USB1") (pin "B3") (pinfunction "D+_B3") (pintype "passive"))
    )
    (net (code "88") (name "/TXD_WIFI") (class "Default")
      (node (ref "ESP1") (pin "35") (pinfunction "TXD0_35") (pintype "passive"))
      (node (ref "PRO") (pin "1") (pinfunction "1_1") (pintype "passive"))
      (node (ref "R5") (pin "1") (pinfunction "1_1") (pintype "passive"))
    )
    (net (code "89") (name "/V9") (class "Default")
      (node (ref "KFIN1") (pin "1") (pinfunction "1_1") (pintype "passive"))
      (node (ref "RZ7") (pin "1") (pinfunction "1_1") (pintype "passive"))
    )
    (net (code "90") (name "/V10") (class "Default")
      (node (ref "KFIN1") (pin "3") (pinfunction "3_3") (pintype "passive"))
      (node (ref "RZ10") (pin "1") (pinfunction "1_1") (pintype "passive"))
    )
    (net (code "91") (name "/V11") (class "Default")
      (node (ref "KFIN1") (pin "5") (pinfunction "5_5") (pintype "passive"))
      (node (ref "RZ13") (pin "1") (pinfunction "1_1") (pintype "passive"))
    )
    (net (code "92") (name "/V12") (class "Default")
      (node (ref "KFIN1") (pin "7") (pinfunction "7_7") (pintype "passive"))
      (node (ref "RZ16") (pin "1") (pinfunction "1_1") (pintype "passive"))
    )
    (net (code "93") (name "/V13") (class "Default")
      (node (ref "KFIN1") (pin "9") (pinfunction "9_9") (pintype "passive"))
      (node (ref "RZ5") (pin "1") (pinfunction "1_1") (pintype "passive"))
    )
    (net (code "94") (name "/V14") (class "Default")
      (node (ref "KFIN1") (pin "11") (pinfunction "11_11") (pintype "passive"))
      (node (ref "RZ8") (pin "1") (pinfunction "1_1") (pintype "passive"))
    )
    (net (code "95") (name "/V15") (class "Default")
      (node (ref "KFIN1") (pin "13") (pinfunction "13_13") (pintype "passive"))
      (node (ref "RZ11") (pin "1") (pinfunction "1_1") (pintype "passive"))
    )
    (net (code "96") (name "/V16") (class "Default")
      (node (ref "KFIN1") (pin "15") (pinfunction "15_15") (pintype "passive"))
      (node (ref "RZ14") (pin "1") (pinfunction "1_1") (pintype "passive"))
    )
    (net (code "97") (name "3.3V") (class "Default")
      (node (ref "C1") (pin "2") (pinfunction "2_2") (pintype "passive"))
      (node (ref "C10") (pin "1") (pinfunction "1_1") (pintype "passive"))
      (node (ref "C11") (pin "2") (pinfunction "2_2") (pintype "passive"))
      (node (ref "ESP1") (pin "2") (pinfunction "3V3_2") (pintype "power_in"))
      (node (ref "HD1") (pin "18") (pinfunction "18_18") (pintype "passive"))
      (node (ref "IC1") (pin "2") (pinfunction "OUT_2") (pintype "passive"))
      (node (ref "IC1") (pin "4") (pinfunction "Tab_4") (pintype "passive"))
      (node (ref "JD211RXASK") (pin "1") (pinfunction "1_1") (pintype "passive"))
      (node (ref "JTX001") (pin "3") (pinfunction "3_3") (pintype "passive"))
      (node (ref "LED18") (pin "1") (pinfunction "1_1") (pintype "passive"))
      (node (ref "OPTO2") (pin "10") (pinfunction "C_10") (pintype "passive"))
      (node (ref "OPTO2") (pin "12") (pinfunction "C_12") (pintype "passive"))
      (node (ref "OPTO2") (pin "14") (pinfunction "C_14") (pintype "passive"))
      (node (ref "OPTO2") (pin "16") (pinfunction "C_16") (pintype "passive"))
      (node (ref "OPTO4") (pin "10") (pinfunction "C_10") (pintype "passive"))
      (node (ref "OPTO4") (pin "12") (pinfunction "C_12") (pintype "passive"))
      (node (ref "OPTO4") (pin "14") (pinfunction "C_14") (pintype "passive"))
      (node (ref "OPTO4") (pin "16") (pinfunction "C_16") (pintype "passive"))
      (node (ref "OUT-DC1") (pin "2") (pinfunction "2_2") (pintype "passive"))
      (node (ref "R2") (pin "2") (pinfunction "2_2") (pintype "passive"))
      (node (ref "R4") (pin "2") (pinfunction "2_2") (pintype "passive"))
      (node (ref "RNT1") (pin "5") (pinfunction "5_5") (pintype "passive"))
      (node (ref "RNT1") (pin "6") (pinfunction "6_6") (pintype "passive"))
      (node (ref "RNT1") (pin "7") (pinfunction "7_7") (pintype "passive"))
      (node (ref "RNT1") (pin "8") (pinfunction "8_8") (pintype "passive"))
      (node (ref "RTC1") (pin "2") (pinfunction "VCC_2") (pintype "passive"))
      (node (ref "SD") (pin "4") (pinfunction "Vdd_4") (pintype "passive"))
      (node (ref "U1") (pin "5") (pinfunction "VCCA_5") (pintype "passive"))
      (node (ref "U1") (pin "6") (pinfunction "OE_6") (pintype "passive"))
      (node (ref "UI1") (pin "24") (pinfunction "VCC_24") (pintype "power_in"))
      (node (ref "USB 1") (pin "1") (pinfunction "VBUS_1") (pintype "passive"))
      (node (ref "USB1") (pin "A1") (pinfunction "VCC_A1") (pintype "passive"))
      (node (ref "USB1") (pin "B1") (pinfunction "VCC_B1") (pintype "passive"))
    )
    (net (code "98") (name "5V") (class "Default")
      (node (ref "C6") (pin "1") (pinfunction "1_1") (pintype "passive"))
      (node (ref "C7") (pin "1") (pinfunction "1_1") (pintype "passive"))
      (node (ref "C8") (pin "1") (pintype "passive"))
      (node (ref "D1") (pin "2") (pinfunction "K_2") (pintype "passive"))
      (node (ref "HD1") (pin "19") (pinfunction "19_19") (pintype "passive"))
      (node (ref "IC1") (pin "3") (pinfunction "IN_3") (pintype "passive"))
      (node (ref "N1") (pin "OV2+") (pinfunction "OV2+_OV2+") (pintype "passive"))
      (node (ref "PRO") (pin "4") (pinfunction "4_4") (pintype "passive"))
      (node (ref "U1") (pin "16") (pinfunction "VCCB_16") (pintype "passive"))
      (node (ref "USB 1") (pin "10") (pinfunction "VBUS_10") (pintype "passive"))
    )
    (net (code "99") (name "12V") (class "Default")
      (node (ref "C12") (pin "1") (pinfunction "1_1") (pintype "passive"))
      (node (ref "C13") (pin "2") (pinfunction "2_2") (pintype "passive"))
      (node (ref "D2") (pin "2") (pinfunction "K_2") (pintype "passive"))
      (node (ref "HD1") (pin "16") (pinfunction "16_16") (pintype "passive"))
      (node (ref "J-IN1") (pin "4") (pinfunction "4_4") (pintype "passive"))
      (node (ref "J-IN1") (pin "5") (pinfunction "5_5") (pintype "passive"))
      (node (ref "N1") (pin "OV1+") (pinfunction "OV1+_OV1+") (pintype "passive"))
    )
    (net (code "100") (name "BGND") (class "Default")
      (node (ref "C12") (pin "2") (pinfunction "2_2") (pintype "passive"))
      (node (ref "C13") (pin "1") (pinfunction "1_1") (pintype "passive"))
      (node (ref "D2") (pin "1") (pinfunction "A_1") (pintype "passive"))
      (node (ref "HD1") (pin "17") (pinfunction "17_17") (pintype "passive"))
      (node (ref "J-IN1") (pin "1") (pinfunction "1_1") (pintype "passive"))
      (node (ref "J-IN1") (pin "2") (pinfunction "2_2") (pintype "passive"))
      (node (ref "N1") (pin "OV1-") (pinfunction "OV1-_OV1-") (pintype "passive"))
    )
    (net (code "101") (name "GND") (class "Default")
      (node (ref "BT1") (pin "2") (pinfunction "GND_2") (pintype "passive"))
      (node (ref "C1") (pin "1") (pinfunction "1_1") (pintype "passive"))
      (node (ref "C10") (pin "2") (pinfunction "2_2") (pintype "passive"))
      (node (ref "C11") (pin "1") (pinfunction "1_1") (pintype "passive"))
      (node (ref "C2") (pin "2") (pinfunction "2_2") (pintype "passive"))
      (node (ref "C3") (pin "1") (pinfunction "1_1") (pintype "passive"))
      (node (ref "C4") (pin "2") (pinfunction "2_2") (pintype "passive"))
      (node (ref "C5") (pin "1") (pinfunction "1_1") (pintype "passive"))
      (node (ref "C6") (pin "2") (pinfunction "2_2") (pintype "passive"))
      (node (ref "C7") (pin "2") (pinfunction "2_2") (pintype "passive"))
      (node (ref "C8") (pin "2") (pintype "passive"))
      (node (ref "D1") (pin "1") (pinfunction "A_1") (pintype "passive"))
      (node (ref "ESP1") (pin "1") (pinfunction "GND_1") (pintype "power_in"))
      (node (ref "ESP1") (pin "15") (pinfunction "GND_15") (pintype "power_in"))
      (node (ref "ESP1") (pin "38") (pinfunction "GND_38") (pintype "power_in"))
      (node (ref "ESP1") (pin "PAD") (pinfunction "GND_PAD") (pintype "power_in"))
      (node (ref "HD1") (pin "20") (pinfunction "20_20") (pintype "passive"))
      (node (ref "IC1") (pin "1") (pinfunction "ADJ/G_1") (pintype "passive"))
      (node (ref "JD211RXASK") (pin "3") (pinfunction "3_3") (pintype "passive"))
      (node (ref "JTX001") (pin "1") (pinfunction "1_1") (pintype "passive"))
      (node (ref "N1") (pin "OV2-") (pinfunction "OV2-_OV2-") (pintype "passive"))
      (node (ref "OUT-DC1") (pin "1") (pinfunction "1_1") (pintype "passive"))
      (node (ref "PRO") (pin "3") (pinfunction "3_3") (pintype "passive"))
      (node (ref "R1") (pin "2") (pinfunction "2_2") (pintype "passive"))
      (node (ref "R3") (pin "2") (pinfunction "2_2") (pintype "passive"))
      (node (ref "R7") (pin "2") (pinfunction "2_2") (pintype "passive"))
      (node (ref "RN3") (pin "1") (pinfunction "1_1") (pintype "passive"))
      (node (ref "RN3") (pin "2") (pinfunction "2_2") (pintype "passive"))
      (node (ref "RN3") (pin "3") (pinfunction "3_3") (pintype "passive"))
      (node (ref "RN3") (pin "4") (pinfunction "4_4") (pintype "passive"))
      (node (ref "RN4") (pin "1") (pinfunction "1_1") (pintype "passive"))
      (node (ref "RN4") (pin "2") (pinfunction "2_2") (pintype "passive"))
      (node (ref "RN4") (pin "3") (pinfunction "3_3") (pintype "passive"))
      (node (ref "RN4") (pin "4") (pinfunction "4_4") (pintype "passive"))
      (node (ref "RST1") (pin "2") (pinfunction "2_2") (pintype "passive"))
      (node (ref "RTC1") (pin "13") (pinfunction "GND_13") (pintype "passive"))
      (node (ref "SD") (pin "6") (pinfunction "Vss_6") (pintype "passive"))
      (node (ref "SD") (pin "Shield") (pinfunction "Shield_Shield") (pintype "passive"))
      (node (ref "SW2") (pin "1") (pinfunction "1_1") (pintype "passive"))
      (node (ref "U1") (pin "15") (pinfunction "GND_15") (pintype "passive"))
      (node (ref "UI1") (pin "12") (pinfunction "GND_12") (pintype "power_in"))
      (node (ref "USB 1") (pin "13") (pinfunction "GND_13") (pintype "passive"))
      (node (ref "USB 1") (pin "4") (pinfunction "GND_4") (pintype "passive"))
      (node (ref "USB 1") (pin "Shell") (pinfunction "Shield_Shell") (pintype "passive"))
      (node (ref "USB1") (pin "A4") (pinfunction "GND_A4") (pintype "passive"))
      (node (ref "USB1") (pin "B4") (pinfunction "GND_B4") (pintype "passive"))
      (node (ref "USB1") (pin "Shell") (pinfunction "Shield_Shell") (pintype "passive"))
    )
    (net (code "102") (name "Net-(BT1-+3V)") (class "Default")
      (node (ref "BT1") (pin "1") (pinfunction "+3V_1") (pintype "passive"))
      (node (ref "RTC1") (pin "14") (pinfunction "VBAT_14") (pintype "passive"))
    )
    (net (code "103") (name "Net-(HD1-Pad9)") (class "Default")
      (node (ref "HD1") (pin "9") (pinfunction "9_9") (pintype "passive"))
      (node (ref "R6") (pin "2") (pinfunction "2_2") (pintype "passive"))
    )
    (net (code "104") (name "Net-(HD1-Pad10)") (class "Default")
      (node (ref "HD1") (pin "10") (pinfunction "10_10") (pintype "passive"))
      (node (ref "R5") (pin "2") (pinfunction "2_2") (pintype "passive"))
    )
    (net (code "105") (name "Net-(LED17-Pad2)") (class "Default")
      (node (ref "LED17") (pin "2") (pinfunction "2_2") (pintype "passive"))
      (node (ref "R1") (pin "1") (pinfunction "1_1") (pintype "passive"))
    )
    (net (code "106") (name "Net-(LED18-Pad2)") (class "Default")
      (node (ref "LED18") (pin "2") (pinfunction "2_2") (pintype "passive"))
      (node (ref "R7") (pin "1") (pinfunction "1_1") (pintype "passive"))
    )
    (net (code "107") (name "unconnected-(ESP1-SCK{slash}CLK-Pad20)") (class "Default")
      (node (ref "ESP1") (pin "20") (pinfunction "SCK/CLK_20") (pintype "passive"))
    )
    (net (code "108") (name "unconnected-(ESP1-SCS{slash}CMD-Pad19)") (class "Default")
      (node (ref "ESP1") (pin "19") (pinfunction "SCS/CMD_19") (pintype "passive"))
    )
    (net (code "109") (name "unconnected-(ESP1-SDI{slash}SD1-Pad22)") (class "Default")
      (node (ref "ESP1") (pin "22") (pinfunction "SDI/SD1_22") (pintype "passive"))
    )
    (net (code "110") (name "unconnected-(ESP1-SDO{slash}SD0-Pad21)") (class "Default")
      (node (ref "ESP1") (pin "21") (pinfunction "SDO/SD0_21") (pintype "passive"))
    )
    (net (code "111") (name "unconnected-(ESP1-SHD{slash}SD2-Pad17)") (class "Default")
      (node (ref "ESP1") (pin "17") (pinfunction "SHD/SD2_17") (pintype "passive"))
    )
    (net (code "112") (name "unconnected-(ESP1-SWP{slash}SD3-Pad18)") (class "Default")
      (node (ref "ESP1") (pin "18") (pinfunction "SWP/SD3_18") (pintype "passive"))
    )
    (net (code "113") (name "unconnected-(RTC1-~{RST}-Pad4)") (class "Default")
      (node (ref "RTC1") (pin "4") (pinfunction "~{RST}_4") (pintype "passive+no_connect"))
    )
    (net (code "114") (name "unconnected-(SD-DAT1-Pad8)") (class "Default")
      (node (ref "SD") (pin "8") (pinfunction "DAT1_8") (pintype "passive"))
    )
    (net (code "115") (name "unconnected-(SD-DAT2-Pad1)") (class "Default")
      (node (ref "SD") (pin "1") (pinfunction "DAT2_1") (pintype "passive"))
    )
    (net (code "116") (name "unconnected-(SW2-Pad3)") (class "Default")
      (node (ref "SW2") (pin "3") (pinfunction "3_3") (pintype "passive"))
    )
    (net (code "117") (name "unconnected-(SW2-Pad4)") (class "Default")
      (node (ref "SW2") (pin "4") (pinfunction "4_4") (pintype "passive"))
    )
  )
)
